# RJ11_BoshBaro_SiHyg.net
KiCad netlist of a schematic drawn in EAGLE
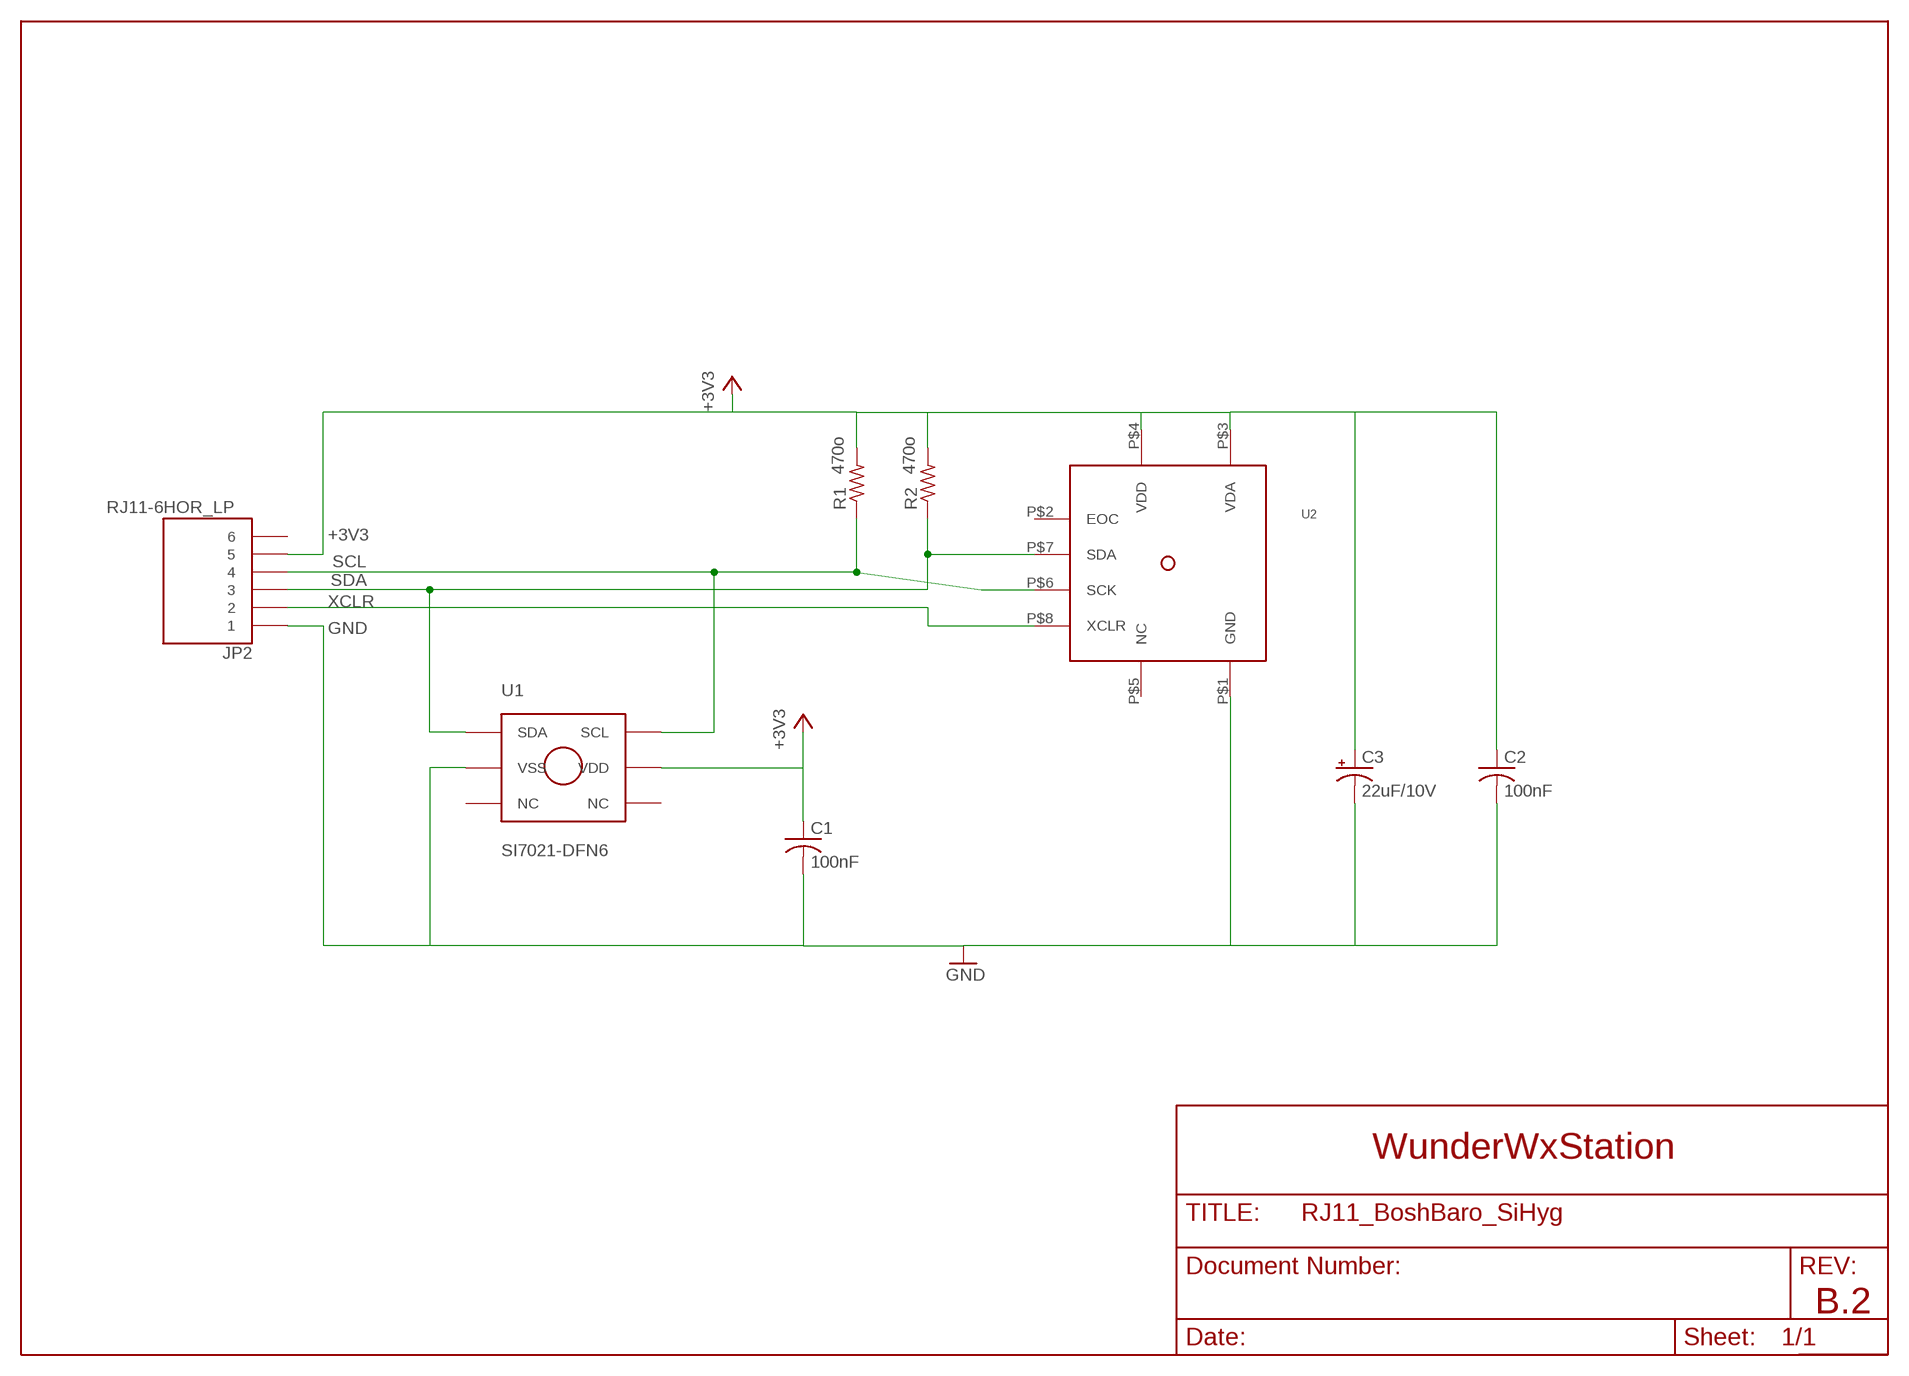
[diagram p0: schematic, sheet 1]

(export (version "E")
  (design (tool "Eeschema 10.0.6"))
  (components
    (comp (ref "C1")
      (value "100nF")
      (footprint "eagle-import:C0805K")
      (libsource (lib "eagle-import") (part "C-USC0805K"))
    )
    (comp (ref "C2")
      (value "100nF")
      (footprint "eagle-import:C0805K")
      (libsource (lib "eagle-import") (part "C-USC0805K"))
    )
    (comp (ref "C3")
      (value "22uF/10V")
      (footprint "eagle-import:SMC_B")
      (libsource (lib "eagle-import") (part "CPOL-USSMCB"))
    )
    (comp (ref "JP2")
      (value "RJ11-6HOR_LP")
      (footprint "eagle-import:RJ11_HOR_LP")
      (libsource (lib "eagle-import") (part "RJ11-6HOR_LP"))
    )
    (comp (ref "R1")
      (value "470o")
      (footprint "eagle-import:R0603")
      (libsource (lib "eagle-import") (part "R-US_R0603"))
    )
    (comp (ref "R2")
      (value "470o")
      (footprint "eagle-import:R0603")
      (libsource (lib "eagle-import") (part "R-US_R0603"))
    )
    (comp (ref "U1")
      (value "SI7021-DFN6")
      (footprint "eagle-import:DFN-6_SILABS")
      (libsource (lib "eagle-import") (part "SI7021-DFN6"))
    )
    (comp (ref "U2")
      (value "BMP085")
      (footprint "eagle-import:LCC8")
      (libsource (lib "eagle-import") (part "BMP085"))
    )
  )
  (nets
    (net (code "1") (name "+3V3") (class "Default")
      (node (ref "C1") (pin "1") (pinfunction "1_1") (pintype "passive"))
      (node (ref "C2") (pin "1") (pinfunction "1_1") (pintype "passive"))
      (node (ref "C3") (pin "+") (pinfunction "+_+") (pintype "passive"))
      (node (ref "JP2") (pin "P$5") (pinfunction "5_P$5") (pintype "bidirectional"))
      (node (ref "R1") (pin "2") (pinfunction "2_2") (pintype "passive"))
      (node (ref "R2") (pin "2") (pinfunction "2_2") (pintype "passive"))
      (node (ref "U1") (pin "P$5") (pinfunction "VDD_P$5") (pintype "power_in"))
      (node (ref "U2") (pin "P$3") (pinfunction "VDA_P$3") (pintype "power_in"))
      (node (ref "U2") (pin "P$4") (pinfunction "VDD_P$4") (pintype "power_in"))
    )
    (net (code "2") (name "/SCL") (class "Default")
      (node (ref "JP2") (pin "P$4") (pinfunction "4_P$4") (pintype "bidirectional"))
      (node (ref "R1") (pin "1") (pinfunction "1_1") (pintype "passive"))
      (node (ref "U1") (pin "P$6") (pinfunction "SCL_P$6") (pintype "bidirectional"))
      (node (ref "U2") (pin "P$6") (pinfunction "SCK_P$6") (pintype "input"))
    )
    (net (code "3") (name "/SDA") (class "Default")
      (node (ref "JP2") (pin "P$3") (pinfunction "3_P$3") (pintype "bidirectional"))
      (node (ref "R2") (pin "1") (pinfunction "1_1") (pintype "passive"))
      (node (ref "U1") (pin "P$1") (pinfunction "SDA_P$1") (pintype "bidirectional"))
      (node (ref "U2") (pin "P$7") (pinfunction "SDA_P$7") (pintype "bidirectional"))
    )
    (net (code "4") (name "/XCLR") (class "Default")
      (node (ref "JP2") (pin "P$2") (pinfunction "2_P$2") (pintype "bidirectional"))
      (node (ref "U2") (pin "P$8") (pinfunction "XCLR_P$8") (pintype "input"))
    )
    (net (code "5") (name "GND") (class "Default")
      (node (ref "C1") (pin "2") (pinfunction "2_2") (pintype "passive"))
      (node (ref "C2") (pin "2") (pinfunction "2_2") (pintype "passive"))
      (node (ref "C3") (pin "-") (pinfunction "-_-") (pintype "passive"))
      (node (ref "JP2") (pin "P$1") (pinfunction "1_P$1") (pintype "bidirectional"))
      (node (ref "U1") (pin "P$2") (pinfunction "VSS_P$2") (pintype "power_in"))
      (node (ref "U2") (pin "P$1") (pinfunction "GND_P$1") (pintype "power_in"))
    )
    (net (code "6") (name "unconnected-(JP2-6-PadP$6)") (class "Default")
      (node (ref "JP2") (pin "P$6") (pinfunction "6_P$6") (pintype "bidirectional"))
    )
    (net (code "7") (name "unconnected-(U1-NC-PadP$3)") (class "Default")
      (node (ref "U1") (pin "P$3") (pinfunction "NC_P$3") (pintype "no_connect"))
    )
    (net (code "8") (name "unconnected-(U1-NC-PadP$4)") (class "Default")
      (node (ref "U1") (pin "P$4") (pinfunction "NC_P$4") (pintype "no_connect"))
    )
    (net (code "9") (name "unconnected-(U2-EOC-PadP$2)") (class "Default")
      (node (ref "U2") (pin "P$2") (pinfunction "EOC_P$2") (pintype "output"))
    )
    (net (code "10") (name "unconnected-(U2-NC-PadP$5)") (class "Default")
      (node (ref "U2") (pin "P$5") (pinfunction "NC_P$5") (pintype "no_connect"))
    )
  )
)
